# NakujaPowerDistributionBoard.net
KiCad netlist of a schematic drawn in EasyEDA
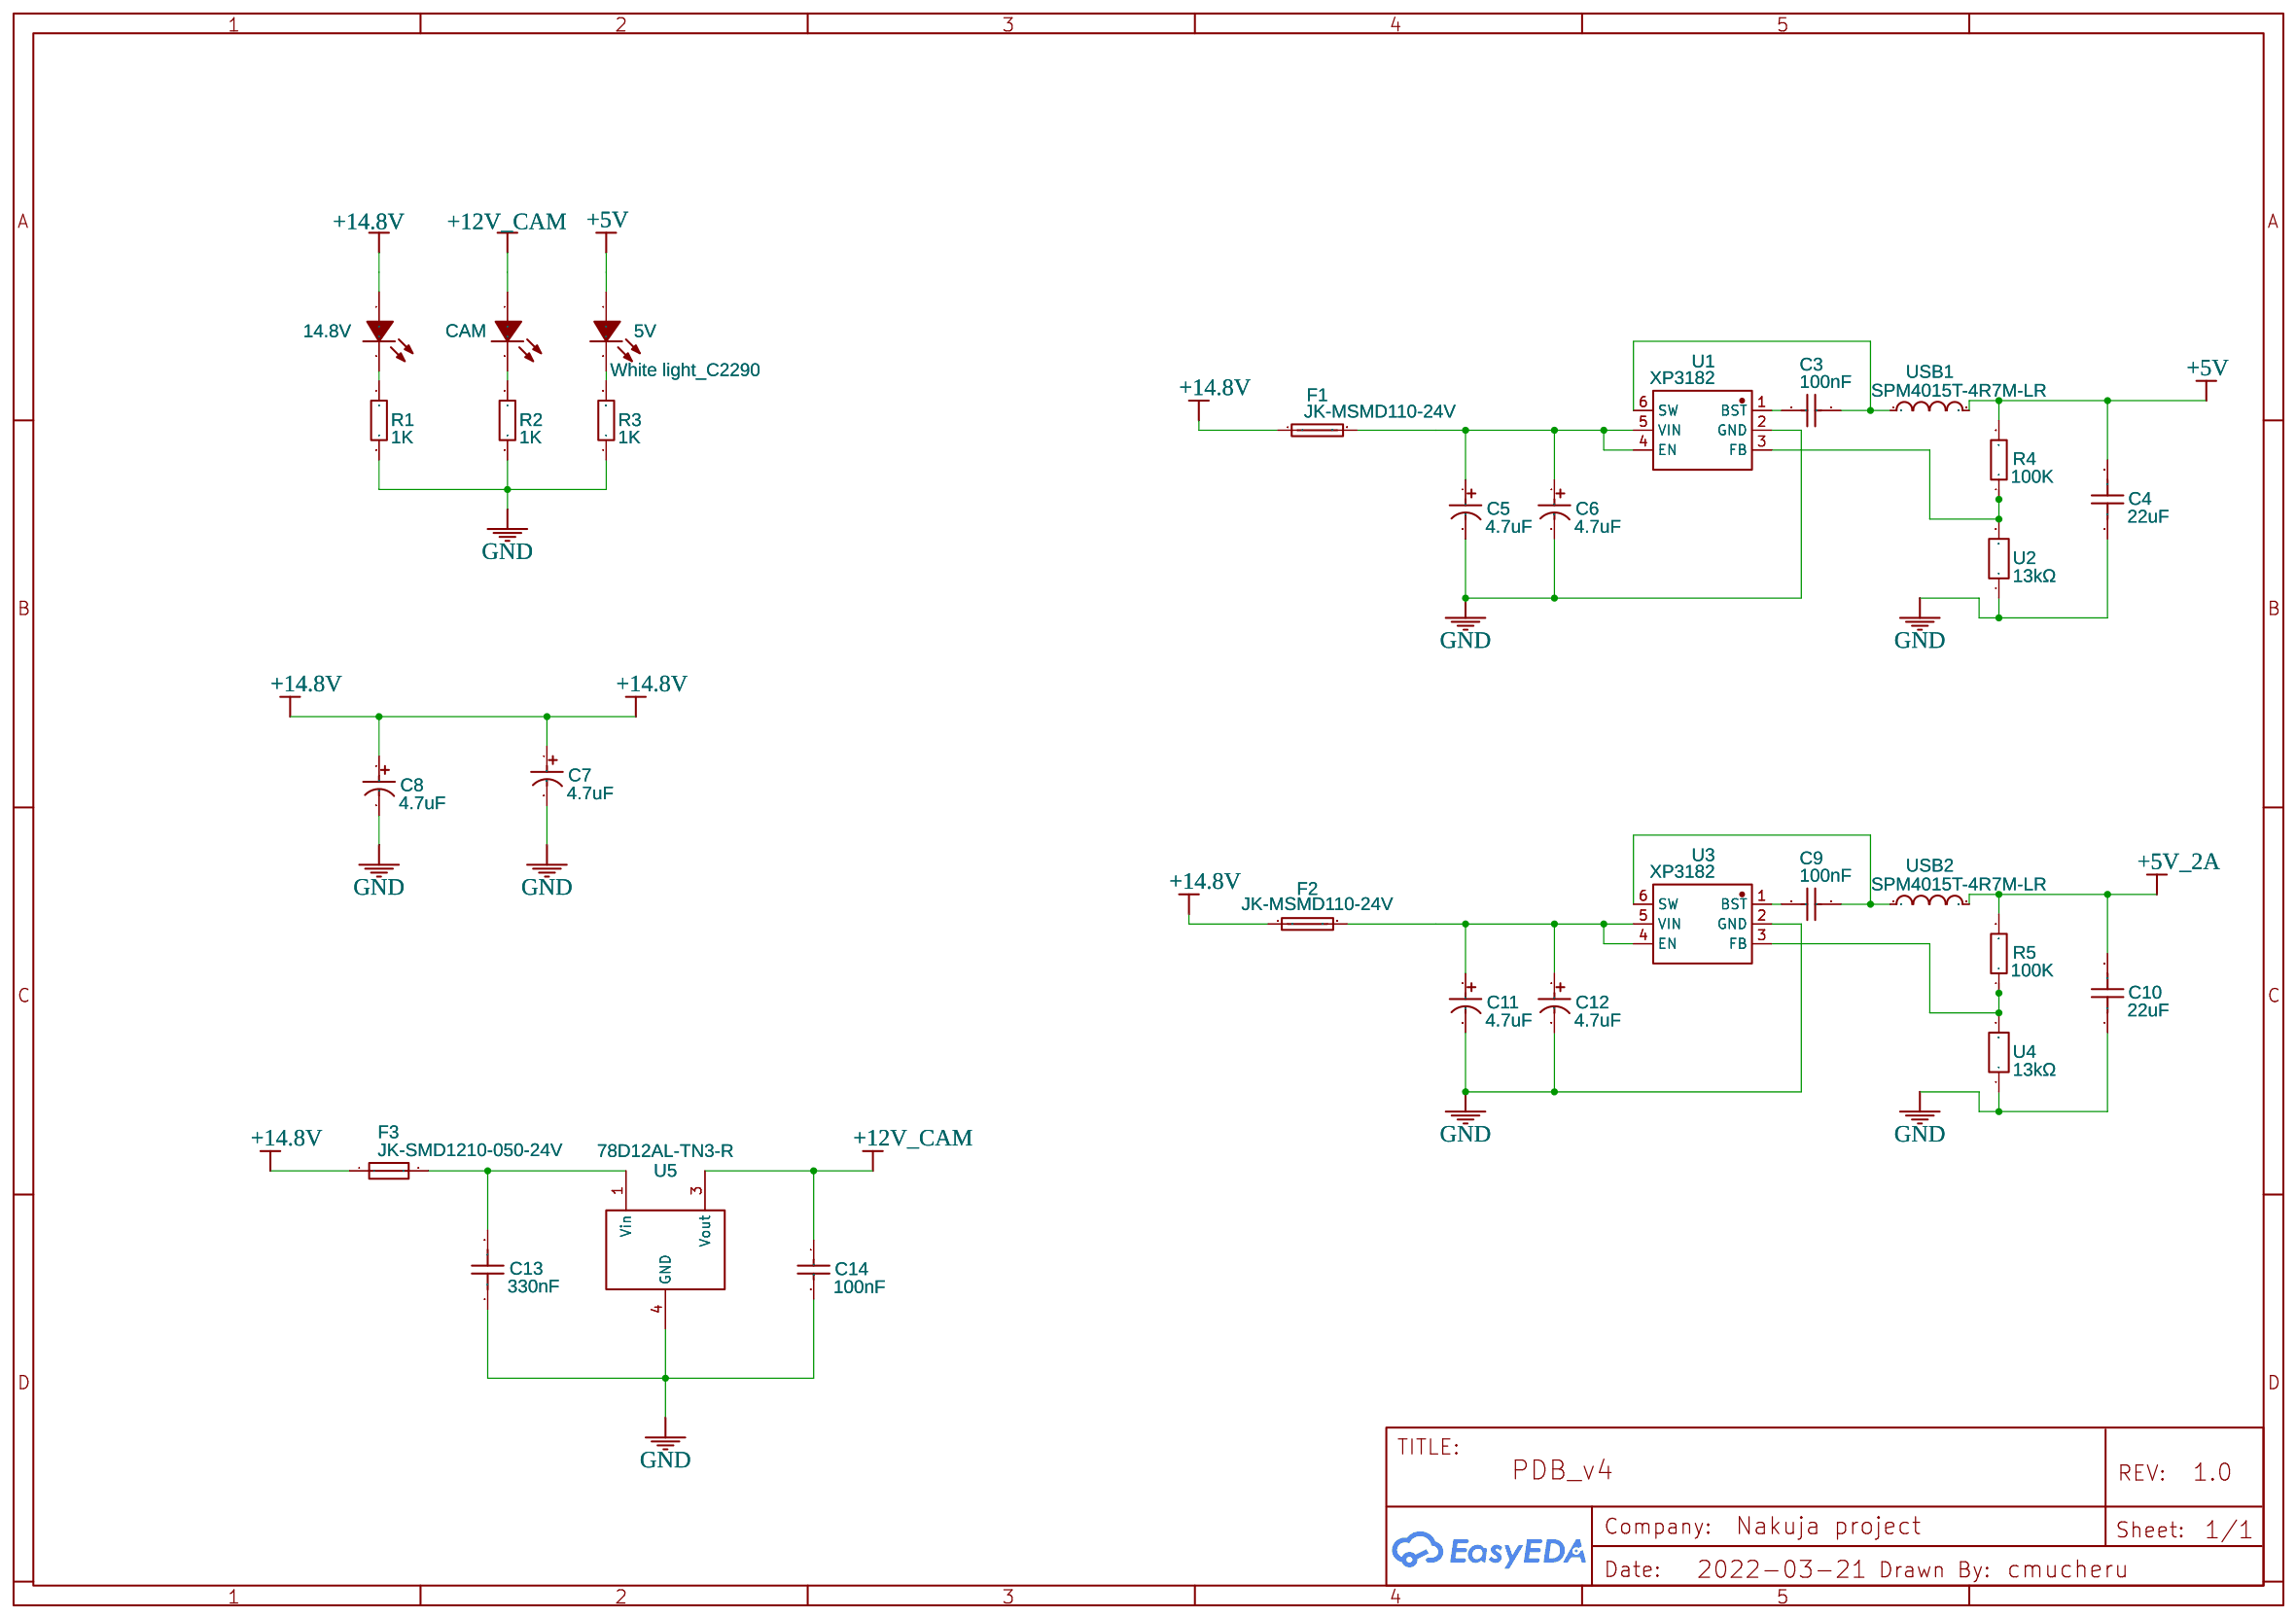
[diagram p0: PDB]
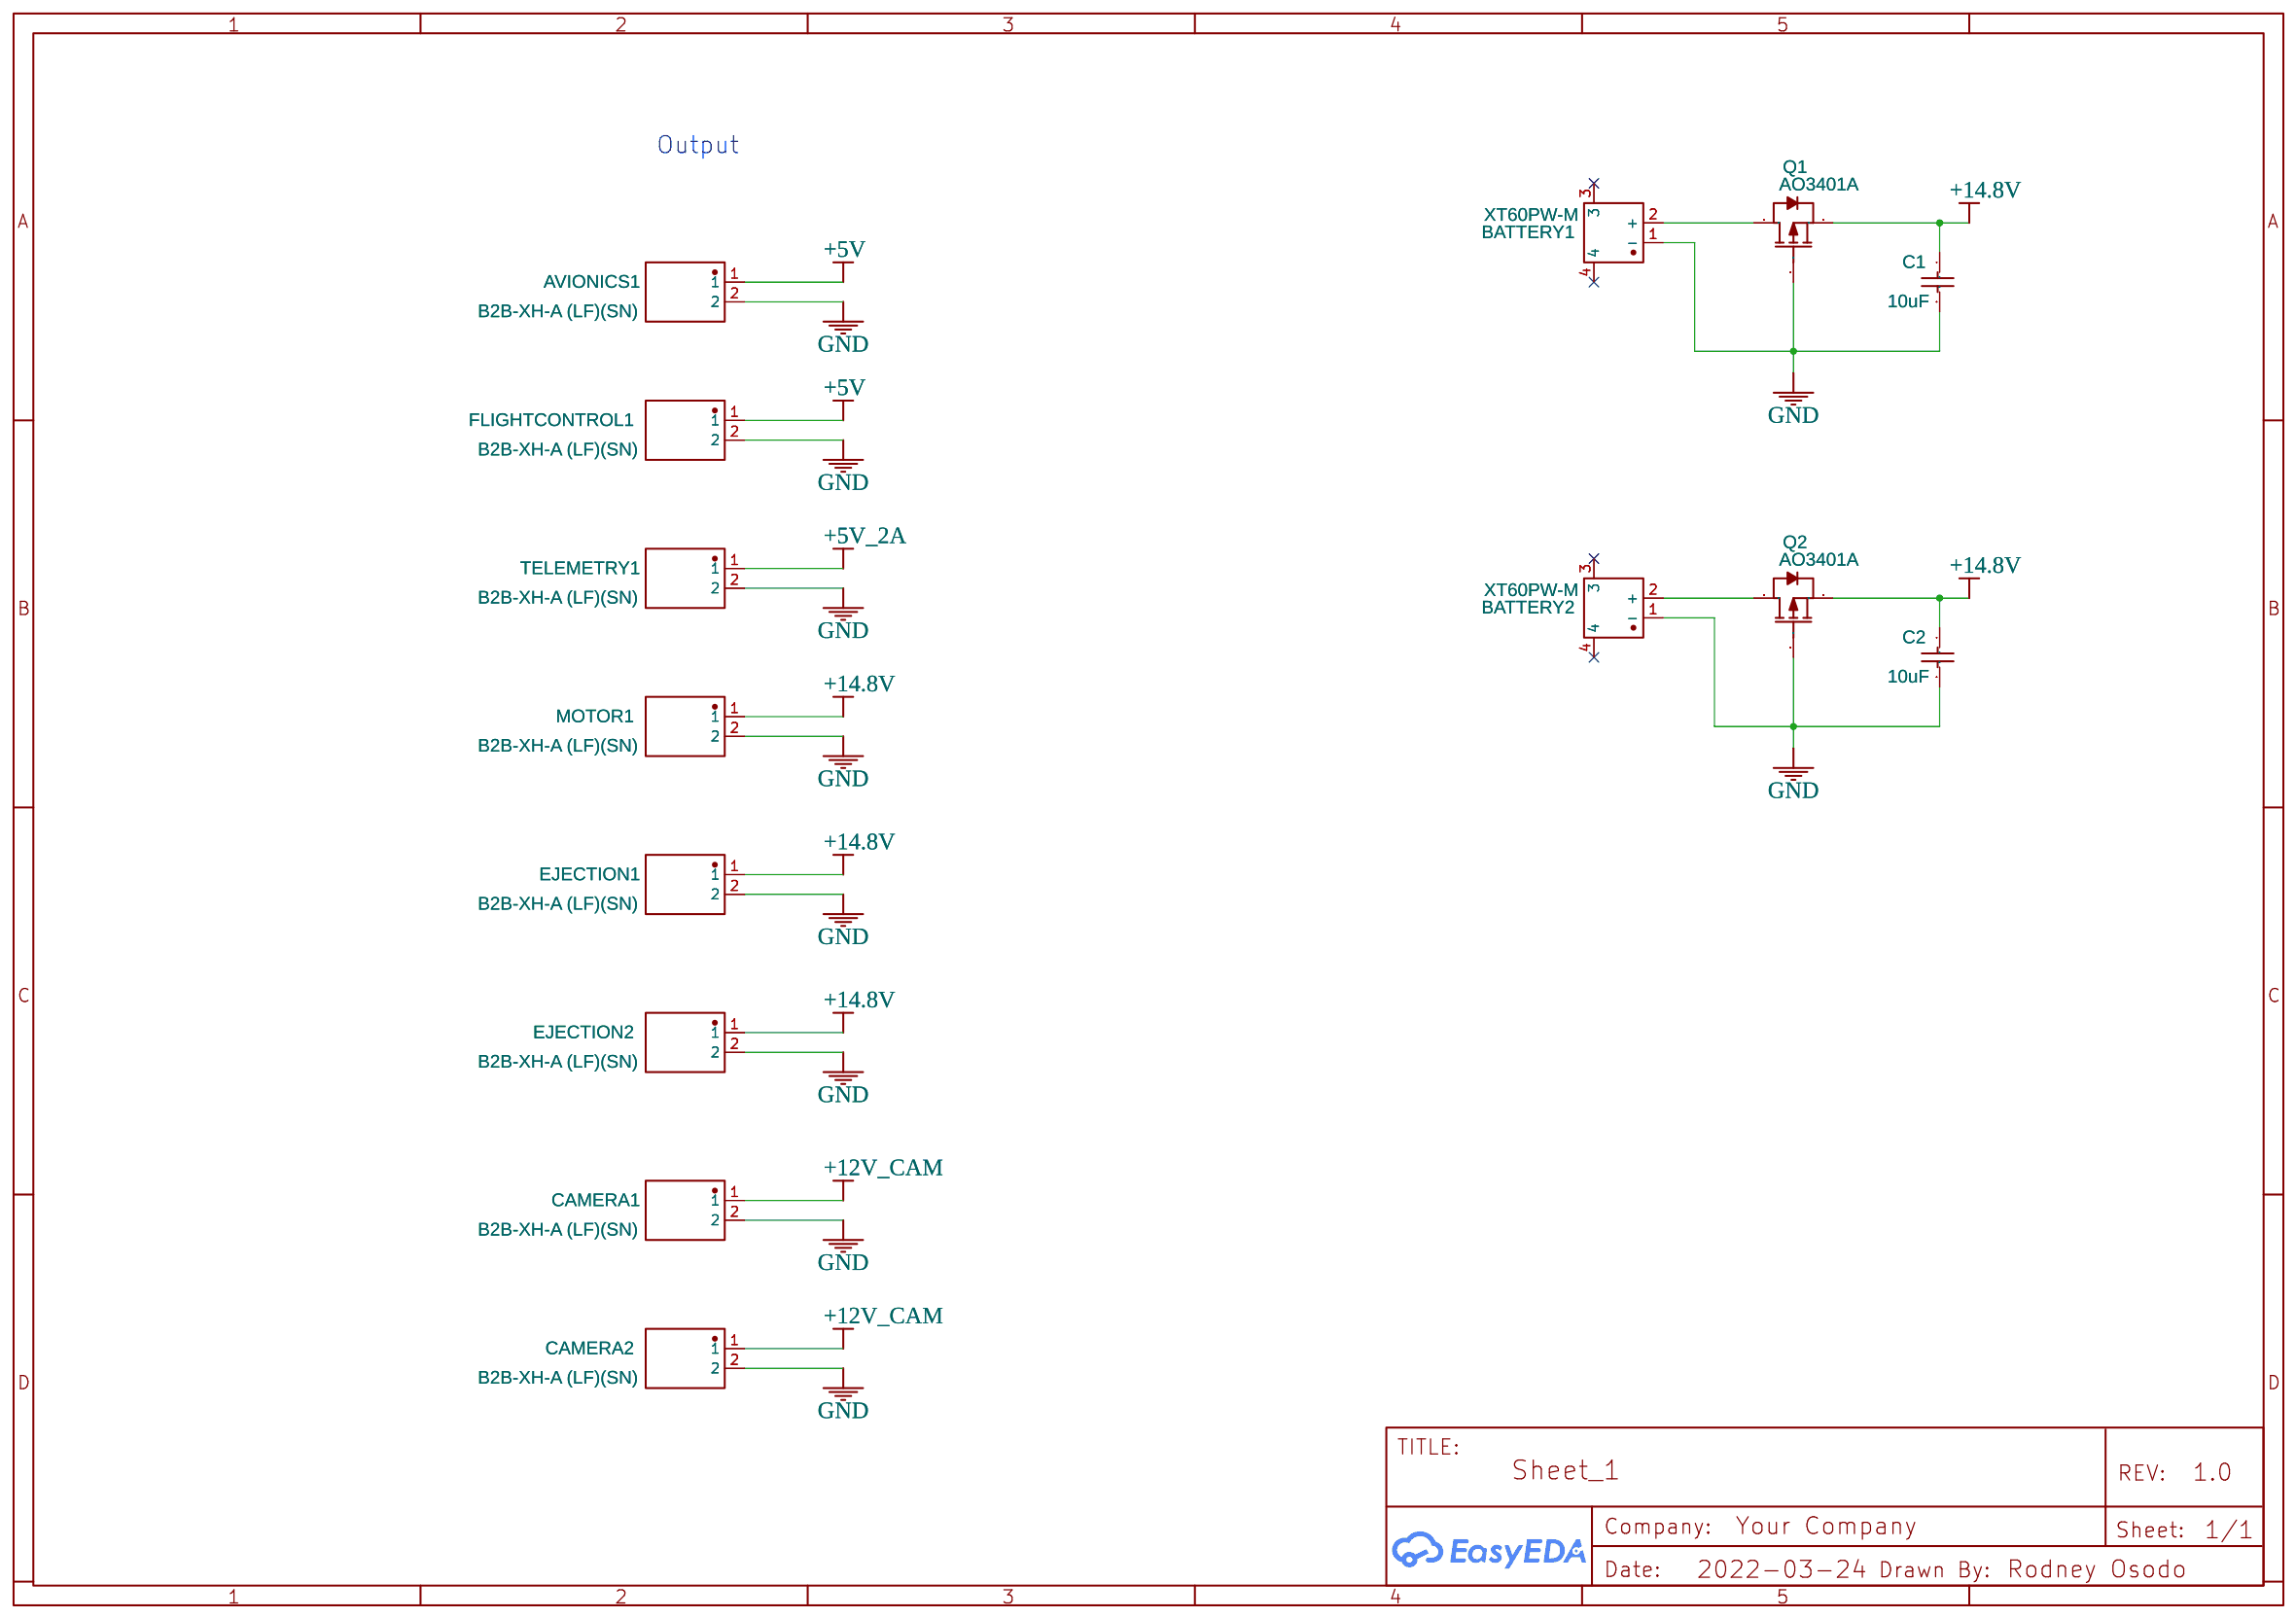
[diagram p1: Connectors]

(export (version "E")
  (design (tool "Eeschema 10.0.6"))
  (components
    (comp (ref "5V")
      (value "White light_C2290")
      (fields
        (field (name "BOM_Manufacturer Part") "0603White light")
        (field (name "BOM_Supplier Part") "C2290")
      )
      (libsource (lib "") (part "0603White light_C2290_2"))
    )
    (comp (ref "14.8V")
      (value "White light_C2290")
      (fields
        (field (name "BOM_Manufacturer Part") "0603White light")
        (field (name "BOM_Supplier Part") "C2290")
      )
      (libsource (lib "") (part "0603White light_C2290_1"))
    )
    (comp (ref "C3")
      (value "100nF")
      (fields
        (field (name "BOM_Manufacturer Part") "CL05B104KO5NNNC")
        (field (name "BOM_Supplier Part") "C1525")
      )
      (libsource (lib "") (part "CL05B104KO5NNNC"))
    )
    (comp (ref "C4")
      (value "22uF")
      (fields
        (field (name "BOM_Manufacturer Part") "GRM155R60J226ME11D")
        (field (name "BOM_Supplier Part") "C415703")
      )
      (libsource (lib "") (part "GRM155R60J226ME11D"))
    )
    (comp (ref "C5")
      (value "4.7uF")
      (fields
        (field (name "BOM_Manufacturer Part") "RVT1V4R7M0405")
        (field (name "BOM_Supplier Part") "C72511")
      )
      (libsource (lib "") (part "RVT1V4R7M0405"))
    )
    (comp (ref "C6")
      (value "4.7uF")
      (fields
        (field (name "BOM_Manufacturer Part") "RVT1V4R7M0405")
        (field (name "BOM_Supplier Part") "C72511")
      )
      (libsource (lib "") (part "RVT1V4R7M0405"))
    )
    (comp (ref "C7")
      (value "4.7uF")
      (fields
        (field (name "BOM_Manufacturer Part") "RVT1V4R7M0405")
        (field (name "BOM_Supplier Part") "C72511")
      )
      (libsource (lib "") (part "RVT1V4R7M0405"))
    )
    (comp (ref "C8")
      (value "4.7uF")
      (fields
        (field (name "BOM_Manufacturer Part") "RVT1V4R7M0405")
        (field (name "BOM_Supplier Part") "C72511")
      )
      (libsource (lib "") (part "RVT1V4R7M0405"))
    )
    (comp (ref "C9")
      (value "100nF")
      (fields
        (field (name "BOM_Manufacturer Part") "CL05B104KO5NNNC")
        (field (name "BOM_Supplier Part") "C1525")
      )
      (libsource (lib "") (part "CL05B104KO5NNNC"))
    )
    (comp (ref "C10")
      (value "22uF")
      (fields
        (field (name "BOM_Manufacturer Part") "GRM155R60J226ME11D")
        (field (name "BOM_Supplier Part") "C415703")
      )
      (libsource (lib "") (part "GRM155R60J226ME11D"))
    )
    (comp (ref "C11")
      (value "4.7uF")
      (fields
        (field (name "BOM_Manufacturer Part") "RVT1V4R7M0405")
        (field (name "BOM_Supplier Part") "C72511")
      )
      (libsource (lib "") (part "RVT1V4R7M0405"))
    )
    (comp (ref "C12")
      (value "4.7uF")
      (fields
        (field (name "BOM_Manufacturer Part") "RVT1V4R7M0405")
        (field (name "BOM_Supplier Part") "C72511")
      )
      (libsource (lib "") (part "RVT1V4R7M0405"))
    )
    (comp (ref "C13")
      (value "330nF")
      (fields
        (field (name "BOM_Manufacturer Part") "CC0402ZRY5V7BB334")
        (field (name "BOM_Supplier Part") "C527033")
      )
      (libsource (lib "") (part "CC0402ZRY5V7BB334"))
    )
    (comp (ref "C14")
      (value "100nF")
      (fields
        (field (name "BOM_Manufacturer Part") "CL05B104KO5NNNC")
        (field (name "BOM_Supplier Part") "C1525")
      )
      (libsource (lib "") (part "CL05B104KO5NNNC_1"))
    )
    (comp (ref "CAM")
      (value "White light_C2290")
      (fields
        (field (name "BOM_Manufacturer Part") "0603White light")
        (field (name "BOM_Supplier Part") "C2290")
      )
      (libsource (lib "") (part "0603White light_C2290"))
    )
    (comp (ref "F1")
      (value "JK-MSMD110-24V")
      (fields (field (name "BOM_Supplier Part") "C369172"))
      (libsource (lib "") (part "JK-MSMD110-24V"))
    )
    (comp (ref "F2")
      (value "JK-MSMD110-24V")
      (fields (field (name "BOM_Supplier Part") "C369172"))
      (libsource (lib "") (part "JK-MSMD110-24V"))
    )
    (comp (ref "F3")
      (value "JK-SMD1210-050-24V")
      (fields (field (name "BOM_Supplier Part") "C720078"))
      (libsource (lib "") (part "JK-SMD1210-050-24V"))
    )
    (comp (ref "R1")
      (value "1K")
      (fields
        (field (name "BOM_Manufacturer Part") "0402WGF5101TCE")
        (field (name "BOM_Supplier Part") "C25905")
      )
      (libsource (lib "") (part "0402WGF5101TCE_1"))
    )
    (comp (ref "R2")
      (value "1K")
      (fields
        (field (name "BOM_Manufacturer Part") "0402WGF5101TCE")
        (field (name "BOM_Supplier Part") "C25905")
      )
      (libsource (lib "") (part "0402WGF5101TCE_1"))
    )
    (comp (ref "R3")
      (value "1K")
      (fields
        (field (name "BOM_Manufacturer Part") "0402WGF5101TCE")
        (field (name "BOM_Supplier Part") "C25905")
      )
      (libsource (lib "") (part "0402WGF5101TCE"))
    )
    (comp (ref "R4")
      (value "100K")
      (fields
        (field (name "BOM_Manufacturer Part") "0402WGF1003TCE")
        (field (name "BOM_Supplier Part") "C25741")
      )
      (libsource (lib "") (part "0402WGF1003TCE"))
    )
    (comp (ref "R5")
      (value "100K")
      (fields
        (field (name "BOM_Manufacturer Part") "0402WGF1003TCE")
        (field (name "BOM_Supplier Part") "C25741")
      )
      (libsource (lib "") (part "0402WGF1003TCE"))
    )
    (comp (ref "U1")
      (value "XP3182")
      (fields (field (name "BOM_Supplier Part") "C2802261"))
      (libsource (lib "") (part "XP3182"))
    )
    (comp (ref "U2")
      (value "13kΩ")
      (fields
        (field (name "BOM_Manufacturer Part") "PTFR0402B13K0P9")
        (field (name "BOM_Supplier Part") "C2693072")
      )
      (libsource (lib "") (part "PTFR0402B13K0P9"))
    )
    (comp (ref "U3")
      (value "XP3182")
      (fields (field (name "BOM_Supplier Part") "C2802261"))
      (libsource (lib "") (part "XP3182"))
    )
    (comp (ref "U4")
      (value "13kΩ")
      (fields
        (field (name "BOM_Manufacturer Part") "PTFR0402B13K0P9")
        (field (name "BOM_Supplier Part") "C2693072")
      )
      (libsource (lib "") (part "PTFR0402B13K0P9"))
    )
    (comp (ref "U5")
      (value "78D12AL-TN3-R")
      (fields (field (name "BOM_Supplier Part") "C73290"))
      (libsource (lib "") (part "78D12AL-TN3-R"))
    )
    (comp (ref "USB1")
      (value "SPM4015T-4R7M-LR")
      (fields (field (name "BOM_Supplier Part") "C2052599"))
      (libsource (lib "") (part "SPM4015T-4R7M-LR"))
    )
    (comp (ref "USB2")
      (value "SPM4015T-4R7M-LR")
      (fields (field (name "BOM_Supplier Part") "C2052599"))
      (libsource (lib "") (part "SPM4015T-4R7M-LR"))
    )
    (comp (ref "AVIONICS1")
      (value "B2B-XH-A (LF)(SN)")
      (fields (field (name "BOM_Supplier Part") "C158012"))
      (libsource (lib "") (part "B2B-XH-A (LF)(SN)_4"))
    )
    (comp (ref "BATTERY1")
      (value "XT60PW-M")
      (fields (field (name "BOM_Supplier Part") "C98732"))
      (libsource (lib "") (part "XT60PW-M"))
    )
    (comp (ref "BATTERY2")
      (value "XT60PW-M")
      (fields (field (name "BOM_Supplier Part") "C98732"))
      (libsource (lib "") (part "XT60PW-M"))
    )
    (comp (ref "C1")
      (value "10uF")
      (fields
        (field (name "BOM_Manufacturer Part") "CL05A106MQ5NUNC")
        (field (name "BOM_Supplier Part") "C15525")
      )
      (libsource (lib "") (part "CL05A106MQ5NUNC"))
    )
    (comp (ref "C2")
      (value "10uF")
      (fields
        (field (name "BOM_Manufacturer Part") "CL05A106MQ5NUNC")
        (field (name "BOM_Supplier Part") "C15525")
      )
      (libsource (lib "") (part "CL05A106MQ5NUNC"))
    )
    (comp (ref "CAMERA1")
      (value "B2B-XH-A (LF)(SN)")
      (fields (field (name "BOM_Supplier Part") "C158012"))
      (libsource (lib "") (part "B2B-XH-A (LF)(SN)_1"))
    )
    (comp (ref "CAMERA2")
      (value "B2B-XH-A (LF)(SN)")
      (fields (field (name "BOM_Supplier Part") "C158012"))
      (libsource (lib "") (part "B2B-XH-A (LF)(SN)_1"))
    )
    (comp (ref "EJECTION1")
      (value "B2B-XH-A (LF)(SN)")
      (fields (field (name "BOM_Supplier Part") "C158012"))
      (libsource (lib "") (part "B2B-XH-A (LF)(SN)_3"))
    )
    (comp (ref "EJECTION2")
      (value "B2B-XH-A (LF)(SN)")
      (fields (field (name "BOM_Supplier Part") "C158012"))
      (libsource (lib "") (part "B2B-XH-A (LF)(SN)_3"))
    )
    (comp (ref "FLIGHTCONTROL1")
      (value "B2B-XH-A (LF)(SN)")
      (fields (field (name "BOM_Supplier Part") "C158012"))
      (libsource (lib "") (part "B2B-XH-A (LF)(SN)"))
    )
    (comp (ref "MOTOR1")
      (value "B2B-XH-A (LF)(SN)")
      (fields (field (name "BOM_Supplier Part") "C158012"))
      (libsource (lib "") (part "B2B-XH-A (LF)(SN)_5"))
    )
    (comp (ref "Q1")
      (value "AO3401A")
      (fields (field (name "BOM_Supplier Part") "C15127"))
      (libsource (lib "") (part "AO3401A"))
    )
    (comp (ref "Q2")
      (value "AO3401A")
      (fields (field (name "BOM_Supplier Part") "C15127"))
      (libsource (lib "") (part "AO3401A"))
    )
    (comp (ref "TELEMETRY1")
      (value "B2B-XH-A (LF)(SN)")
      (fields (field (name "BOM_Supplier Part") "C158012"))
      (libsource (lib "") (part "B2B-XH-A (LF)(SN)_2"))
    )
  )
  (nets
    (net (code "1") (name "+5V") (class "Default")
      (node (ref "5V") (pin "1") (pinfunction "A_1") (pintype "unspecified"))
      (node (ref "AVIONICS1") (pin "1") (pinfunction "1_1") (pintype "unspecified"))
      (node (ref "C4") (pin "2") (pinfunction "2_2") (pintype "unspecified"))
      (node (ref "FLIGHTCONTROL1") (pin "1") (pinfunction "1_1") (pintype "unspecified"))
      (node (ref "R4") (pin "2") (pinfunction "2_2") (pintype "input"))
      (node (ref "USB1") (pin "2") (pinfunction "2_2") (pintype "unspecified"))
    )
    (net (code "2") (name "+5V_2A") (class "Default")
      (node (ref "C10") (pin "2") (pinfunction "2_2") (pintype "unspecified"))
      (node (ref "R5") (pin "2") (pinfunction "2_2") (pintype "input"))
      (node (ref "TELEMETRY1") (pin "1") (pinfunction "1_1") (pintype "unspecified"))
      (node (ref "USB2") (pin "2") (pinfunction "2_2") (pintype "unspecified"))
    )
    (net (code "3") (name "+12V_CAM") (class "Default")
      (node (ref "C14") (pin "1") (pinfunction "1_1") (pintype "input"))
      (node (ref "CAM") (pin "1") (pinfunction "A_1") (pintype "unspecified"))
      (node (ref "CAMERA1") (pin "1") (pinfunction "1_1") (pintype "unspecified"))
      (node (ref "CAMERA2") (pin "1") (pinfunction "1_1") (pintype "unspecified"))
      (node (ref "U5") (pin "3") (pinfunction "Vout_3") (pintype "unspecified"))
    )
    (net (code "4") (name "+14.8V") (class "Default")
      (node (ref "14.8V") (pin "1") (pinfunction "A_1") (pintype "unspecified"))
      (node (ref "C1") (pin "1") (pinfunction "1_1") (pintype "input"))
      (node (ref "C2") (pin "1") (pinfunction "1_1") (pintype "input"))
      (node (ref "C7") (pin "1") (pinfunction "1_1") (pintype "input"))
      (node (ref "C8") (pin "1") (pinfunction "1_1") (pintype "input"))
      (node (ref "EJECTION1") (pin "1") (pinfunction "1_1") (pintype "unspecified"))
      (node (ref "EJECTION2") (pin "1") (pinfunction "1_1") (pintype "unspecified"))
      (node (ref "F1") (pin "1") (pinfunction "1_1") (pintype "unspecified"))
      (node (ref "F2") (pin "1") (pinfunction "1_1") (pintype "unspecified"))
      (node (ref "F3") (pin "1") (pinfunction "1_1") (pintype "unspecified"))
      (node (ref "MOTOR1") (pin "1") (pinfunction "1_1") (pintype "unspecified"))
      (node (ref "Q1") (pin "2") (pinfunction "S_2") (pintype "unspecified"))
      (node (ref "Q2") (pin "2") (pinfunction "S_2") (pintype "unspecified"))
    )
    (net (code "5") (name "GND") (class "Default")
      (node (ref "AVIONICS1") (pin "2") (pinfunction "2_2") (pintype "unspecified"))
      (node (ref "BATTERY1") (pin "1") (pinfunction "-_1") (pintype "unspecified"))
      (node (ref "BATTERY2") (pin "1") (pinfunction "-_1") (pintype "unspecified"))
      (node (ref "C1") (pin "2") (pinfunction "2_2") (pintype "input"))
      (node (ref "C10") (pin "1") (pinfunction "1_1") (pintype "unspecified"))
      (node (ref "C11") (pin "2") (pinfunction "2_2") (pintype "input"))
      (node (ref "C12") (pin "2") (pinfunction "2_2") (pintype "input"))
      (node (ref "C13") (pin "1") (pinfunction "1_1") (pintype "unspecified"))
      (node (ref "C14") (pin "2") (pinfunction "2_2") (pintype "input"))
      (node (ref "C2") (pin "2") (pinfunction "2_2") (pintype "input"))
      (node (ref "C4") (pin "1") (pinfunction "1_1") (pintype "unspecified"))
      (node (ref "C5") (pin "2") (pinfunction "2_2") (pintype "input"))
      (node (ref "C6") (pin "2") (pinfunction "2_2") (pintype "input"))
      (node (ref "C7") (pin "2") (pinfunction "2_2") (pintype "input"))
      (node (ref "C8") (pin "2") (pinfunction "2_2") (pintype "input"))
      (node (ref "CAMERA1") (pin "2") (pinfunction "2_2") (pintype "unspecified"))
      (node (ref "CAMERA2") (pin "2") (pinfunction "2_2") (pintype "unspecified"))
      (node (ref "EJECTION1") (pin "2") (pinfunction "2_2") (pintype "unspecified"))
      (node (ref "EJECTION2") (pin "2") (pinfunction "2_2") (pintype "unspecified"))
      (node (ref "FLIGHTCONTROL1") (pin "2") (pinfunction "2_2") (pintype "unspecified"))
      (node (ref "MOTOR1") (pin "2") (pinfunction "2_2") (pintype "unspecified"))
      (node (ref "Q1") (pin "1") (pinfunction "G_1") (pintype "unspecified"))
      (node (ref "Q2") (pin "1") (pinfunction "G_1") (pintype "unspecified"))
      (node (ref "R1") (pin "2") (pinfunction "2_2") (pintype "input"))
      (node (ref "R2") (pin "2") (pinfunction "2_2") (pintype "input"))
      (node (ref "R3") (pin "1") (pinfunction "1_1") (pintype "input"))
      (node (ref "TELEMETRY1") (pin "2") (pinfunction "2_2") (pintype "unspecified"))
      (node (ref "U1") (pin "2") (pinfunction "GND_2") (pintype "unspecified"))
      (node (ref "U2") (pin "1") (pinfunction "1_1") (pintype "unspecified"))
      (node (ref "U3") (pin "2") (pinfunction "GND_2") (pintype "unspecified"))
      (node (ref "U4") (pin "1") (pinfunction "1_1") (pintype "unspecified"))
      (node (ref "U5") (pin "4") (pinfunction "GND_4") (pintype "unspecified"))
    )
    (net (code "6") (name "Net-(5V-K)") (class "Default")
      (node (ref "5V") (pin "2") (pinfunction "K_2") (pintype "unspecified"))
      (node (ref "R3") (pin "2") (pinfunction "2_2") (pintype "input"))
    )
    (net (code "7") (name "Net-(14.8V-K)") (class "Default")
      (node (ref "14.8V") (pin "2") (pinfunction "K_2") (pintype "unspecified"))
      (node (ref "R1") (pin "1") (pinfunction "1_1") (pintype "input"))
    )
    (net (code "8") (name "Net-(BATTERY1-+)") (class "Default")
      (node (ref "BATTERY1") (pin "2") (pinfunction "+_2") (pintype "unspecified"))
      (node (ref "Q1") (pin "3") (pinfunction "D_3") (pintype "unspecified"))
    )
    (net (code "9") (name "Net-(BATTERY2-+)") (class "Default")
      (node (ref "BATTERY2") (pin "2") (pinfunction "+_2") (pintype "unspecified"))
      (node (ref "Q2") (pin "3") (pinfunction "D_3") (pintype "unspecified"))
    )
    (net (code "10") (name "Net-(CAM-K)") (class "Default")
      (node (ref "CAM") (pin "2") (pinfunction "K_2") (pintype "unspecified"))
      (node (ref "R2") (pin "1") (pinfunction "1_1") (pintype "input"))
    )
    (net (code "11") (name "Net-(U1-BST)") (class "Default")
      (node (ref "C3") (pin "2") (pinfunction "2_2") (pintype "input"))
      (node (ref "U1") (pin "1") (pinfunction "BST_1") (pintype "unspecified"))
    )
    (net (code "12") (name "Net-(U1-EN)") (class "Default")
      (node (ref "C5") (pin "1") (pinfunction "1_1") (pintype "input"))
      (node (ref "C6") (pin "1") (pinfunction "1_1") (pintype "input"))
      (node (ref "F1") (pin "2") (pinfunction "2_2") (pintype "unspecified"))
      (node (ref "U1") (pin "4") (pinfunction "EN_4") (pintype "unspecified"))
      (node (ref "U1") (pin "5") (pinfunction "VIN_5") (pintype "unspecified"))
    )
    (net (code "13") (name "Net-(U1-FB)") (class "Default")
      (node (ref "R4") (pin "1") (pinfunction "1_1") (pintype "input"))
      (node (ref "U1") (pin "3") (pinfunction "FB_3") (pintype "unspecified"))
      (node (ref "U2") (pin "2") (pinfunction "2_2") (pintype "unspecified"))
    )
    (net (code "14") (name "Net-(U1-SW)") (class "Default")
      (node (ref "C3") (pin "1") (pinfunction "1_1") (pintype "input"))
      (node (ref "U1") (pin "6") (pinfunction "SW_6") (pintype "unspecified"))
      (node (ref "USB1") (pin "1") (pinfunction "1_1") (pintype "unspecified"))
    )
    (net (code "15") (name "Net-(U3-BST)") (class "Default")
      (node (ref "C9") (pin "2") (pinfunction "2_2") (pintype "input"))
      (node (ref "U3") (pin "1") (pinfunction "BST_1") (pintype "unspecified"))
    )
    (net (code "16") (name "Net-(U3-EN)") (class "Default")
      (node (ref "C11") (pin "1") (pinfunction "1_1") (pintype "input"))
      (node (ref "C12") (pin "1") (pinfunction "1_1") (pintype "input"))
      (node (ref "F2") (pin "2") (pinfunction "2_2") (pintype "unspecified"))
      (node (ref "U3") (pin "4") (pinfunction "EN_4") (pintype "unspecified"))
      (node (ref "U3") (pin "5") (pinfunction "VIN_5") (pintype "unspecified"))
    )
    (net (code "17") (name "Net-(U3-FB)") (class "Default")
      (node (ref "R5") (pin "1") (pinfunction "1_1") (pintype "input"))
      (node (ref "U3") (pin "3") (pinfunction "FB_3") (pintype "unspecified"))
      (node (ref "U4") (pin "2") (pinfunction "2_2") (pintype "unspecified"))
    )
    (net (code "18") (name "Net-(U3-SW)") (class "Default")
      (node (ref "C9") (pin "1") (pinfunction "1_1") (pintype "input"))
      (node (ref "U3") (pin "6") (pinfunction "SW_6") (pintype "unspecified"))
      (node (ref "USB2") (pin "1") (pinfunction "1_1") (pintype "unspecified"))
    )
    (net (code "19") (name "Net-(U5-Vin)") (class "Default")
      (node (ref "C13") (pin "2") (pinfunction "2_2") (pintype "unspecified"))
      (node (ref "F3") (pin "2") (pinfunction "2_2") (pintype "unspecified"))
      (node (ref "U5") (pin "1") (pinfunction "Vin_1") (pintype "unspecified"))
    )
    (net (code "20") (name "unconnected-(BATTERY1-Pad3)") (class "Default")
      (node (ref "BATTERY1") (pin "3") (pinfunction "3_3") (pintype "unspecified+no_connect"))
    )
    (net (code "21") (name "unconnected-(BATTERY1-Pad4)") (class "Default")
      (node (ref "BATTERY1") (pin "4") (pinfunction "4_4") (pintype "unspecified+no_connect"))
    )
    (net (code "22") (name "unconnected-(BATTERY2-Pad3)") (class "Default")
      (node (ref "BATTERY2") (pin "3") (pinfunction "3_3") (pintype "unspecified+no_connect"))
    )
    (net (code "23") (name "unconnected-(BATTERY2-Pad4)") (class "Default")
      (node (ref "BATTERY2") (pin "4") (pinfunction "4_4") (pintype "unspecified+no_connect"))
    )
  )
)
